# Lightpack5_6.net
KiCad netlist of a schematic drawn in EAGLE
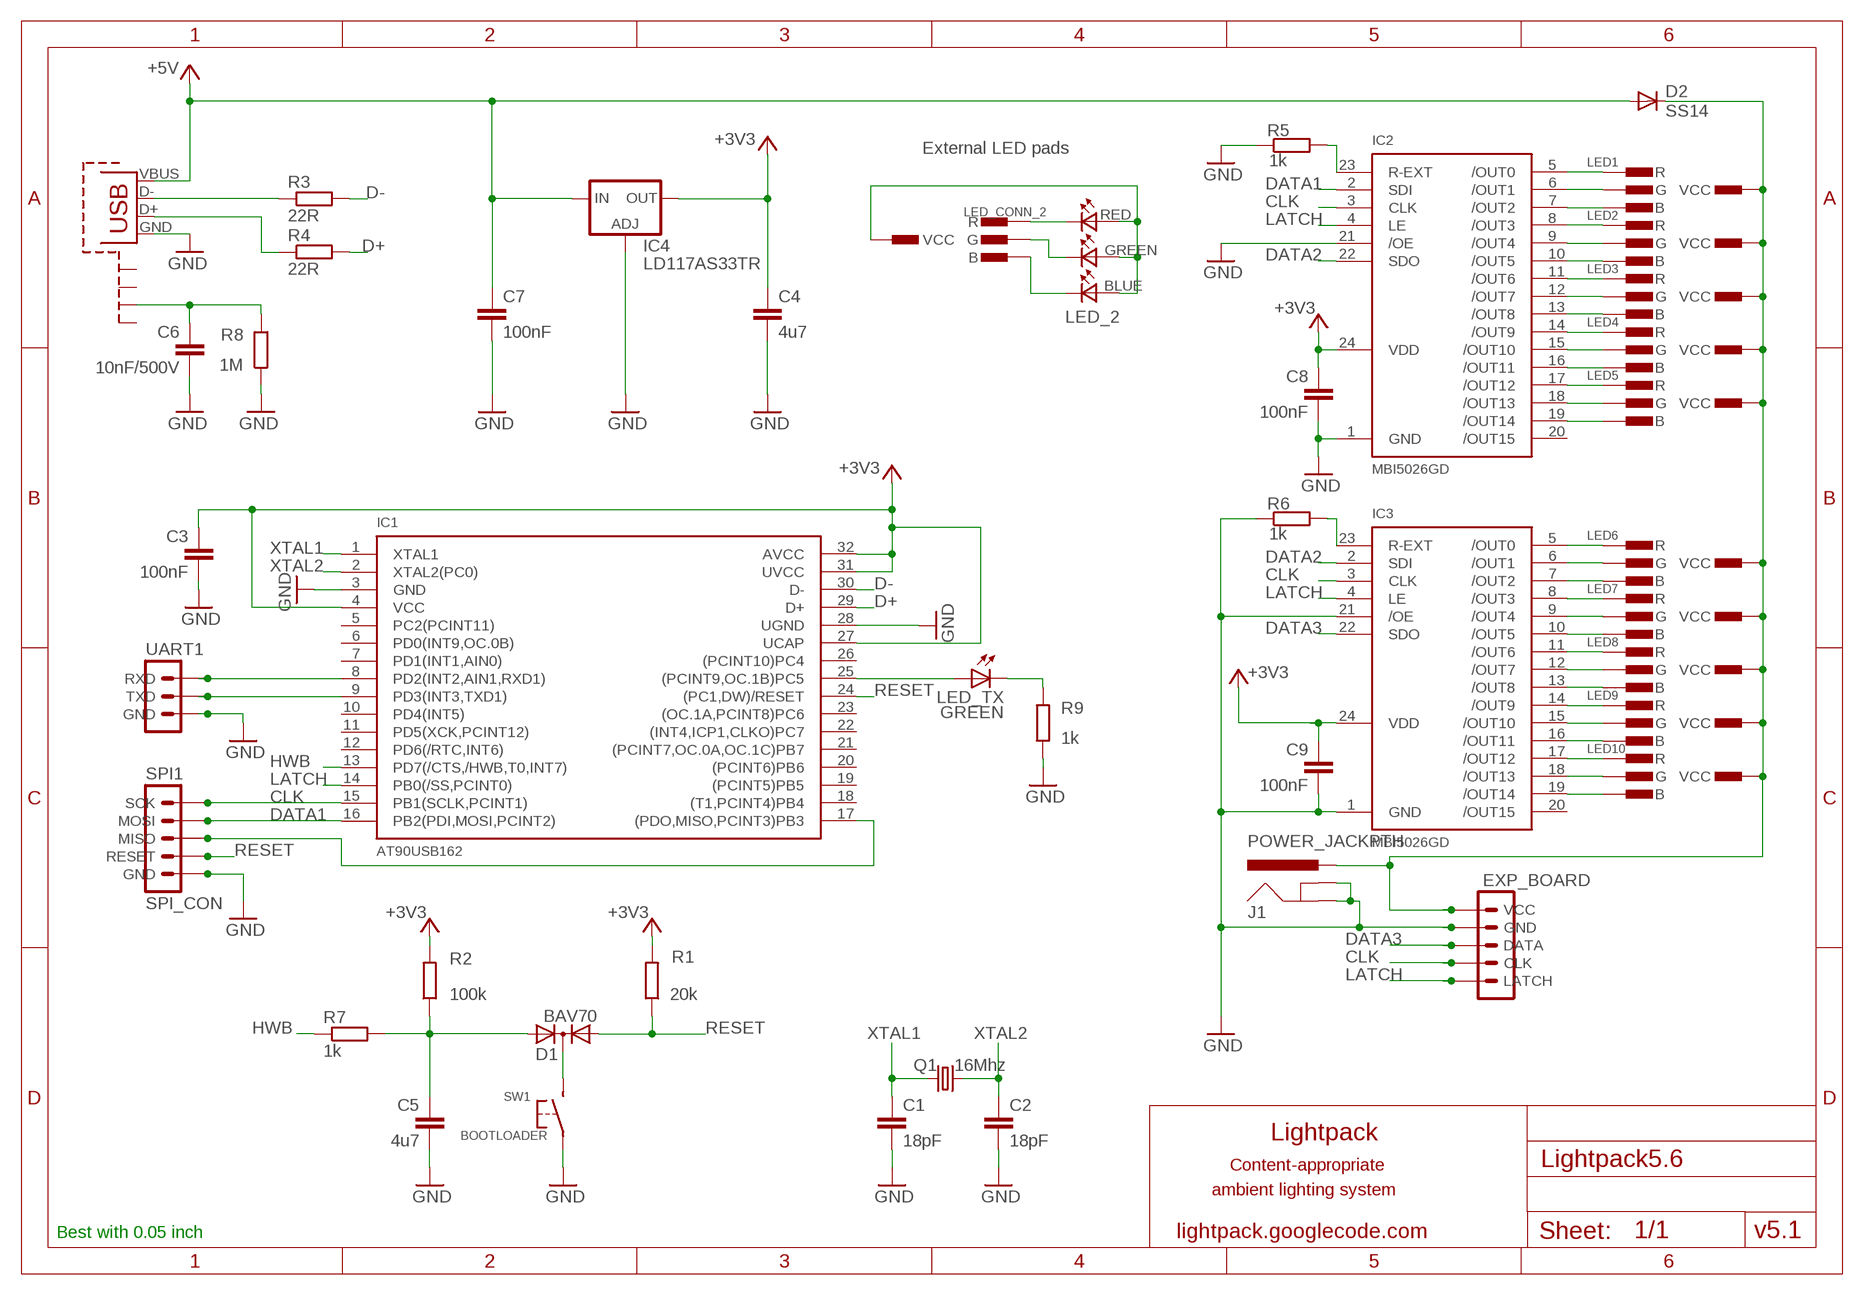
[diagram p0: schematic, sheet 1]

(export (version "E")
  (design (tool "Eeschema 10.0.6"))
  (components
    (comp (ref "C1")
      (value "18pF")
      (footprint "eagle-import:C1206")
      (libsource (lib "eagle-import") (part "C-EUC1206"))
    )
    (comp (ref "C2")
      (value "18pF")
      (footprint "eagle-import:C1206")
      (libsource (lib "eagle-import") (part "C-EUC1206"))
    )
    (comp (ref "C3")
      (value "100nF")
      (footprint "eagle-import:C1206")
      (libsource (lib "eagle-import") (part "C-EUC1206"))
    )
    (comp (ref "C4")
      (value "4u7")
      (footprint "eagle-import:C1206")
      (libsource (lib "eagle-import") (part "C-EUC1206"))
    )
    (comp (ref "C5")
      (value "4u7")
      (footprint "eagle-import:C1206")
      (libsource (lib "eagle-import") (part "C-EUC1206"))
    )
    (comp (ref "C6")
      (value "10nF/500V")
      (footprint "eagle-import:C1206")
      (libsource (lib "eagle-import") (part "C-EUC1206"))
    )
    (comp (ref "C7")
      (value "100nF")
      (footprint "eagle-import:C1206")
      (libsource (lib "eagle-import") (part "C-EUC1206"))
    )
    (comp (ref "C8")
      (value "100nF")
      (footprint "eagle-import:C1206")
      (libsource (lib "eagle-import") (part "C-EUC1206"))
    )
    (comp (ref "C9")
      (value "100nF")
      (footprint "eagle-import:C1206")
      (libsource (lib "eagle-import") (part "C-EUC1206"))
    )
    (comp (ref "D1")
      (value "BAV70")
      (footprint "eagle-import:SOT23")
      (libsource (lib "eagle-import") (part "DIODE-2AC|CASOT23"))
    )
    (comp (ref "D2")
      (value "SS14")
      (footprint "eagle-import:SMB")
      (libsource (lib "eagle-import") (part "DIODE-SMB"))
    )
    (comp (ref "EXP_BOARD")
      (value "MA05-1")
      (footprint "eagle-import:MA05-1")
      (libsource (lib "eagle-import") (part "MA05-1"))
    )
    (comp (ref "IC1")
      (value "AT90USB162")
      (footprint "eagle-import:TQFP32")
      (libsource (lib "eagle-import") (part "AT90USB162"))
    )
    (comp (ref "IC2")
      (value "MBI5026GD")
      (footprint "eagle-import:SOP24-300-1.27")
      (libsource (lib "eagle-import") (part "MBI5026GD"))
    )
    (comp (ref "IC3")
      (value "MBI5026GD")
      (footprint "eagle-import:SOP24-300-1.27")
      (libsource (lib "eagle-import") (part "MBI5026GD"))
    )
    (comp (ref "IC4")
      (value "LD117AS33TR")
      (footprint "eagle-import:SOT223")
      (libsource (lib "eagle-import") (part "LD117A?S33TR"))
    )
    (comp (ref "J1")
      (value "POWER_JACKPTH")
      (footprint "eagle-import:POWER_JACK_PTH")
      (libsource (lib "eagle-import") (part "POWER_JACKPTH"))
    )
    (comp (ref "LED1")
      (value "CON-RGB-LED")
      (footprint "eagle-import:CON-RGB-LED-TH")
      (libsource (lib "eagle-import") (part "CON-RGB-LED-TH"))
    )
    (comp (ref "LED2")
      (value "CON-RGB-LED")
      (footprint "eagle-import:CON-RGB-LED-TH")
      (libsource (lib "eagle-import") (part "CON-RGB-LED-TH"))
    )
    (comp (ref "LED3")
      (value "CON-RGB-LED")
      (footprint "eagle-import:CON-RGB-LED-TH")
      (libsource (lib "eagle-import") (part "CON-RGB-LED-TH"))
    )
    (comp (ref "LED4")
      (value "CON-RGB-LED")
      (footprint "eagle-import:CON-RGB-LED-TH")
      (libsource (lib "eagle-import") (part "CON-RGB-LED-TH"))
    )
    (comp (ref "LED5")
      (value "CON-RGB-LED")
      (footprint "eagle-import:CON-RGB-LED-TH")
      (libsource (lib "eagle-import") (part "CON-RGB-LED-TH"))
    )
    (comp (ref "LED6")
      (value "CON-RGB-LED")
      (footprint "eagle-import:CON-RGB-LED-TH")
      (libsource (lib "eagle-import") (part "CON-RGB-LED-TH"))
    )
    (comp (ref "LED7")
      (value "CON-RGB-LED")
      (footprint "eagle-import:CON-RGB-LED-TH")
      (libsource (lib "eagle-import") (part "CON-RGB-LED-TH"))
    )
    (comp (ref "LED8")
      (value "CON-RGB-LED")
      (footprint "eagle-import:CON-RGB-LED-TH")
      (libsource (lib "eagle-import") (part "CON-RGB-LED-TH"))
    )
    (comp (ref "LED9")
      (value "CON-RGB-LED")
      (footprint "eagle-import:CON-RGB-LED-TH")
      (libsource (lib "eagle-import") (part "CON-RGB-LED-TH"))
    )
    (comp (ref "LED10")
      (value "CON-RGB-LED")
      (footprint "eagle-import:CON-RGB-LED-TH")
      (libsource (lib "eagle-import") (part "CON-RGB-LED-TH"))
    )
    (comp (ref "LED_2")
      (value "TOPLED-3RF-W2SA50TS")
      (footprint "eagle-import:LP2C63-ST-RGB-SR0")
      (libsource (lib "eagle-import") (part "TOPLED-3RF-W2SA50TS"))
    )
    (comp (ref "LED_CONN_2")
      (value "CON-RGB-LED")
      (footprint "eagle-import:CON-RGB-LED-TH-EXT")
      (libsource (lib "eagle-import") (part "CON-RGB-LED-EXT"))
    )
    (comp (ref "LED_TX")
      (value "GREEN")
      (footprint "eagle-import:CHIPLED_0805")
      (libsource (lib "eagle-import") (part "LEDCHIPLED_0805"))
    )
    (comp (ref "Q1")
      (value "16Mhz")
      (footprint "eagle-import:HC49UP")
      (libsource (lib "eagle-import") (part "CRYSTALHC49UP"))
    )
    (comp (ref "R1")
      (value "20k")
      (footprint "eagle-import:R1206")
      (libsource (lib "eagle-import") (part "R-EU_R1206"))
    )
    (comp (ref "R2")
      (value "100k")
      (footprint "eagle-import:R1206")
      (libsource (lib "eagle-import") (part "R-EU_R1206_2"))
    )
    (comp (ref "R3")
      (value "22R")
      (footprint "eagle-import:R1206")
      (libsource (lib "eagle-import") (part "rcl_R-EU_R1206"))
    )
    (comp (ref "R4")
      (value "22R")
      (footprint "eagle-import:R1206")
      (libsource (lib "eagle-import") (part "rcl_R-EU_R1206"))
    )
    (comp (ref "R5")
      (value "1k")
      (footprint "eagle-import:R1206")
      (libsource (lib "eagle-import") (part "R-EU_R1206"))
    )
    (comp (ref "R6")
      (value "1k")
      (footprint "eagle-import:R1206")
      (libsource (lib "eagle-import") (part "R-EU_R1206"))
    )
    (comp (ref "R7")
      (value "1k")
      (footprint "eagle-import:R1206")
      (libsource (lib "eagle-import") (part "rcl_R-EU_R1206"))
    )
    (comp (ref "R8")
      (value "1M")
      (footprint "eagle-import:R1206")
      (libsource (lib "eagle-import") (part "rcl_R-EU_R1206"))
    )
    (comp (ref "R9")
      (value "1k")
      (footprint "eagle-import:R1206")
      (libsource (lib "eagle-import") (part "rcl_R-EU_R1206"))
    )
    (comp (ref "SPI1")
      (value "SPI_CON")
      (footprint "eagle-import:NXT_BRD")
      (libsource (lib "eagle-import") (part "SPI_CON"))
    )
    (comp (ref "SW1")
      (value "BOOTLOADER")
      (footprint "eagle-import:BUTTON-SMD")
      (libsource (lib "eagle-import") (part "BUTTON"))
    )
    (comp (ref "UART1")
      (value "UART3")
      (footprint "eagle-import:UART3")
      (libsource (lib "eagle-import") (part "UART3"))
    )
    (comp (ref "X1")
      (value "USB-MB-S")
      (footprint "eagle-import:USB-MB-S")
      (libsource (lib "eagle-import") (part "USB-MB-S"))
    )
  )
  (nets
    (net (code "1") (name "+3V3") (class "Default")
      (node (ref "C3") (pin "1") (pinfunction "1_1") (pintype "passive"))
      (node (ref "C4") (pin "1") (pinfunction "1_1") (pintype "passive"))
      (node (ref "C8") (pin "1") (pinfunction "1_1") (pintype "passive"))
      (node (ref "C9") (pin "1") (pinfunction "1_1") (pintype "passive"))
      (node (ref "IC1") (pin "27") (pinfunction "UCAP_27") (pintype "bidirectional"))
      (node (ref "IC1") (pin "31") (pinfunction "UVCC_31") (pintype "bidirectional"))
      (node (ref "IC1") (pin "32") (pinfunction "AVCC_32") (pintype "bidirectional"))
      (node (ref "IC1") (pin "4") (pinfunction "VCC_4") (pintype "bidirectional"))
      (node (ref "IC2") (pin "24") (pinfunction "VDD_24") (pintype "bidirectional"))
      (node (ref "IC3") (pin "24") (pinfunction "VDD_24") (pintype "bidirectional"))
      (node (ref "IC4") (pin "4") (pinfunction "OUT_4") (pintype "passive"))
      (node (ref "R1") (pin "2") (pinfunction "2_2") (pintype "passive"))
      (node (ref "R2") (pin "1") (pinfunction "2_1") (pintype "passive"))
    )
    (net (code "2") (name "+5V") (class "Default")
      (node (ref "C7") (pin "1") (pinfunction "1_1") (pintype "passive"))
      (node (ref "D2") (pin "A") (pinfunction "A_A") (pintype "passive"))
      (node (ref "IC4") (pin "3") (pinfunction "IN_3") (pintype "input"))
      (node (ref "X1") (pin "VBUS") (pinfunction "VBUS_VBUS") (pintype "bidirectional"))
    )
    (net (code "3") (name "/CLK") (class "Default")
      (node (ref "EXP_BOARD") (pin "2") (pinfunction "CLK_2") (pintype "passive"))
      (node (ref "IC1") (pin "15") (pinfunction "PB1(SCLK,PCINT1)_15") (pintype "bidirectional"))
      (node (ref "IC2") (pin "3") (pinfunction "CLK_3") (pintype "bidirectional"))
      (node (ref "IC3") (pin "3") (pinfunction "CLK_3") (pintype "bidirectional"))
      (node (ref "SPI1") (pin "2") (pinfunction "SCK_2") (pintype "passive"))
    )
    (net (code "4") (name "/D+") (class "Default")
      (node (ref "IC1") (pin "29") (pinfunction "D+_29") (pintype "bidirectional"))
      (node (ref "R4") (pin "2") (pinfunction "2_2") (pintype "passive"))
    )
    (net (code "5") (name "/D-") (class "Default")
      (node (ref "IC1") (pin "30") (pinfunction "D-_30") (pintype "bidirectional"))
      (node (ref "R3") (pin "2") (pinfunction "2_2") (pintype "passive"))
    )
    (net (code "6") (name "/DATA1") (class "Default")
      (node (ref "IC1") (pin "16") (pinfunction "PB2(PDI,MOSI,PCINT2)_16") (pintype "bidirectional"))
      (node (ref "IC2") (pin "2") (pinfunction "SDI_2") (pintype "bidirectional"))
      (node (ref "SPI1") (pin "3") (pinfunction "MOSI_3") (pintype "passive"))
    )
    (net (code "7") (name "/DATA2") (class "Default")
      (node (ref "IC2") (pin "22") (pinfunction "SDO_22") (pintype "bidirectional"))
      (node (ref "IC3") (pin "2") (pinfunction "SDI_2") (pintype "bidirectional"))
    )
    (net (code "8") (name "/DATA3") (class "Default")
      (node (ref "EXP_BOARD") (pin "3") (pinfunction "DATA_3") (pintype "passive"))
      (node (ref "IC3") (pin "22") (pinfunction "SDO_22") (pintype "bidirectional"))
    )
    (net (code "9") (name "/HWB") (class "Default")
      (node (ref "IC1") (pin "13") (pinfunction "PD7(/CTS,/HWB,T0,INT7)_13") (pintype "bidirectional"))
      (node (ref "R7") (pin "1") (pinfunction "1_1") (pintype "passive"))
    )
    (net (code "10") (name "/LATCH") (class "Default")
      (node (ref "EXP_BOARD") (pin "1") (pinfunction "LATCH_1") (pintype "passive"))
      (node (ref "IC1") (pin "14") (pinfunction "PB0(/SS,PCINT0)_14") (pintype "bidirectional"))
      (node (ref "IC2") (pin "4") (pinfunction "LE_4") (pintype "bidirectional"))
      (node (ref "IC3") (pin "4") (pinfunction "LE_4") (pintype "bidirectional"))
    )
    (net (code "11") (name "/RESET") (class "Default")
      (node (ref "D1") (pin "1") (pinfunction "A1_1") (pintype "passive"))
      (node (ref "IC1") (pin "24") (pinfunction "(PC1,DW)/RESET_24") (pintype "bidirectional"))
      (node (ref "R1") (pin "1") (pinfunction "1_1") (pintype "passive"))
      (node (ref "SPI1") (pin "5-R") (pinfunction "RESET_5-R") (pintype "passive"))
    )
    (net (code "12") (name "/XTAL1") (class "Default")
      (node (ref "C1") (pin "1") (pinfunction "1_1") (pintype "passive"))
      (node (ref "IC1") (pin "1") (pinfunction "XTAL1_1") (pintype "bidirectional"))
      (node (ref "Q1") (pin "1") (pinfunction "1_1") (pintype "passive"))
    )
    (net (code "13") (name "/XTAL2") (class "Default")
      (node (ref "C2") (pin "1") (pinfunction "1_1") (pintype "passive"))
      (node (ref "IC1") (pin "2") (pinfunction "XTAL2(PC0)_2") (pintype "bidirectional"))
      (node (ref "Q1") (pin "2") (pinfunction "2_2") (pintype "passive"))
    )
    (net (code "14") (name "GND") (class "Default")
      (node (ref "C1") (pin "2") (pinfunction "2_2") (pintype "passive"))
      (node (ref "C2") (pin "2") (pinfunction "2_2") (pintype "passive"))
      (node (ref "C3") (pin "2") (pinfunction "2_2") (pintype "passive"))
      (node (ref "C4") (pin "2") (pinfunction "2_2") (pintype "passive"))
      (node (ref "C5") (pin "2") (pinfunction "2_2") (pintype "passive"))
      (node (ref "C6") (pin "2") (pinfunction "2_2") (pintype "passive"))
      (node (ref "C7") (pin "2") (pinfunction "2_2") (pintype "passive"))
      (node (ref "C8") (pin "2") (pinfunction "2_2") (pintype "passive"))
      (node (ref "C9") (pin "2") (pinfunction "2_2") (pintype "passive"))
      (node (ref "EXP_BOARD") (pin "4") (pinfunction "GND_4") (pintype "passive"))
      (node (ref "IC1") (pin "28") (pinfunction "UGND_28") (pintype "bidirectional"))
      (node (ref "IC1") (pin "3") (pinfunction "GND_3") (pintype "bidirectional"))
      (node (ref "IC2") (pin "1") (pinfunction "GND_1") (pintype "bidirectional"))
      (node (ref "IC2") (pin "21") (pinfunction "/OE_21") (pintype "bidirectional"))
      (node (ref "IC3") (pin "1") (pinfunction "GND_1") (pintype "bidirectional"))
      (node (ref "IC3") (pin "21") (pinfunction "/OE_21") (pintype "bidirectional"))
      (node (ref "IC4") (pin "1") (pinfunction "ADJ_1") (pintype "input"))
      (node (ref "J1") (pin "GND") (pinfunction "GND_GND") (pintype "bidirectional"))
      (node (ref "J1") (pin "GNDBREAK") (pinfunction "GNDBREAK_GNDBREAK") (pintype "bidirectional"))
      (node (ref "R5") (pin "1") (pinfunction "1_1") (pintype "passive"))
      (node (ref "R6") (pin "1") (pinfunction "1_1") (pintype "passive"))
      (node (ref "R8") (pin "1") (pinfunction "1_1") (pintype "passive"))
      (node (ref "R9") (pin "1") (pinfunction "1_1") (pintype "passive"))
      (node (ref "SPI1") (pin "1-L") (pinfunction "GND_1-L") (pintype "passive"))
      (node (ref "SW1") (pin "1") (pinfunction "1_1") (pintype "passive"))
      (node (ref "UART1") (pin "1-L") (pinfunction "GND_1-L") (pintype "passive"))
      (node (ref "X1") (pin "GND") (pinfunction "GND_GND") (pintype "bidirectional"))
    )
    (net (code "15") (name "Net-(C6-Pad1)") (class "Default")
      (node (ref "C6") (pin "1") (pinfunction "1_1") (pintype "passive"))
      (node (ref "R8") (pin "2") (pinfunction "2_2") (pintype "passive"))
      (node (ref "X1") (pin "SHIELD3") (pinfunction "SHIELD3_SHIELD3") (pintype "bidirectional"))
    )
    (net (code "16") (name "Net-(D1-A2)") (class "Default")
      (node (ref "C5") (pin "1") (pinfunction "1_1") (pintype "passive"))
      (node (ref "D1") (pin "2") (pinfunction "A2_2") (pintype "passive"))
      (node (ref "R2") (pin "2") (pinfunction "1_2") (pintype "passive"))
      (node (ref "R7") (pin "2") (pinfunction "2_2") (pintype "passive"))
    )
    (net (code "17") (name "Net-(D1-C)") (class "Default")
      (node (ref "D1") (pin "3") (pinfunction "C_3") (pintype "passive"))
      (node (ref "SW1") (pin "2") (pinfunction "2_2") (pintype "passive"))
    )
    (net (code "18") (name "Net-(EXP_BOARD-VCC)") (class "Default")
      (node (ref "D2") (pin "C") (pinfunction "C_C") (pintype "passive"))
      (node (ref "EXP_BOARD") (pin "5") (pinfunction "VCC_5") (pintype "passive"))
      (node (ref "J1") (pin "PWR") (pinfunction "PWR_PWR") (pintype "bidirectional"))
      (node (ref "LED1") (pin "4.VCC") (pinfunction "VCC_4.VCC") (pintype "bidirectional"))
      (node (ref "LED10") (pin "4.VCC") (pinfunction "VCC_4.VCC") (pintype "bidirectional"))
      (node (ref "LED2") (pin "4.VCC") (pinfunction "VCC_4.VCC") (pintype "bidirectional"))
      (node (ref "LED3") (pin "4.VCC") (pinfunction "VCC_4.VCC") (pintype "bidirectional"))
      (node (ref "LED4") (pin "4.VCC") (pinfunction "VCC_4.VCC") (pintype "bidirectional"))
      (node (ref "LED5") (pin "4.VCC") (pinfunction "VCC_4.VCC") (pintype "bidirectional"))
      (node (ref "LED6") (pin "4.VCC") (pinfunction "VCC_4.VCC") (pintype "bidirectional"))
      (node (ref "LED7") (pin "4.VCC") (pinfunction "VCC_4.VCC") (pintype "bidirectional"))
      (node (ref "LED8") (pin "4.VCC") (pinfunction "VCC_4.VCC") (pintype "bidirectional"))
      (node (ref "LED9") (pin "4.VCC") (pinfunction "VCC_4.VCC") (pintype "bidirectional"))
    )
    (net (code "19") (name "Net-(IC1-(PCINT9,OC.1B)PC5)") (class "Default")
      (node (ref "IC1") (pin "25") (pinfunction "(PCINT9,OC.1B)PC5_25") (pintype "bidirectional"))
      (node (ref "LED_TX") (pin "A") (pinfunction "A_A") (pintype "passive"))
    )
    (net (code "20") (name "Net-(IC1-(PDO,MISO,PCINT3)PB3)") (class "Default")
      (node (ref "IC1") (pin "17") (pinfunction "(PDO,MISO,PCINT3)PB3_17") (pintype "bidirectional"))
      (node (ref "SPI1") (pin "4") (pinfunction "MISO_4") (pintype "passive"))
    )
    (net (code "21") (name "Net-(IC1-PD2(INT2,AIN1,RXD1))") (class "Default")
      (node (ref "IC1") (pin "8") (pinfunction "PD2(INT2,AIN1,RXD1)_8") (pintype "bidirectional"))
      (node (ref "UART1") (pin "2") (pinfunction "RXD_2") (pintype "passive"))
    )
    (net (code "22") (name "Net-(IC1-PD3(INT3,TXD1))") (class "Default")
      (node (ref "IC1") (pin "9") (pinfunction "PD3(INT3,TXD1)_9") (pintype "bidirectional"))
      (node (ref "UART1") (pin "3-R") (pinfunction "TXD_3-R") (pintype "passive"))
    )
    (net (code "23") (name "Net-(IC2-R-EXT)") (class "Default")
      (node (ref "IC2") (pin "23") (pinfunction "R-EXT_23") (pintype "bidirectional"))
      (node (ref "R5") (pin "2") (pinfunction "2_2") (pintype "passive"))
    )
    (net (code "24") (name "Net-(IC2-{slash}OUT0)") (class "Default")
      (node (ref "IC2") (pin "5") (pinfunction "/OUT0_5") (pintype "bidirectional"))
      (node (ref "LED1") (pin "3.R") (pinfunction "R_3.R") (pintype "bidirectional"))
    )
    (net (code "25") (name "Net-(IC2-{slash}OUT1)") (class "Default")
      (node (ref "IC2") (pin "6") (pinfunction "/OUT1_6") (pintype "bidirectional"))
      (node (ref "LED1") (pin "2.G") (pinfunction "G_2.G") (pintype "bidirectional"))
    )
    (net (code "26") (name "Net-(IC2-{slash}OUT2)") (class "Default")
      (node (ref "IC2") (pin "7") (pinfunction "/OUT2_7") (pintype "bidirectional"))
      (node (ref "LED1") (pin "1.B") (pinfunction "B_1.B") (pintype "bidirectional"))
    )
    (net (code "27") (name "Net-(IC2-{slash}OUT3)") (class "Default")
      (node (ref "IC2") (pin "8") (pinfunction "/OUT3_8") (pintype "bidirectional"))
      (node (ref "LED2") (pin "3.R") (pinfunction "R_3.R") (pintype "bidirectional"))
    )
    (net (code "28") (name "Net-(IC2-{slash}OUT4)") (class "Default")
      (node (ref "IC2") (pin "9") (pinfunction "/OUT4_9") (pintype "bidirectional"))
      (node (ref "LED2") (pin "2.G") (pinfunction "G_2.G") (pintype "bidirectional"))
    )
    (net (code "29") (name "Net-(IC2-{slash}OUT5)") (class "Default")
      (node (ref "IC2") (pin "10") (pinfunction "/OUT5_10") (pintype "bidirectional"))
      (node (ref "LED2") (pin "1.B") (pinfunction "B_1.B") (pintype "bidirectional"))
    )
    (net (code "30") (name "Net-(IC2-{slash}OUT6)") (class "Default")
      (node (ref "IC2") (pin "11") (pinfunction "/OUT6_11") (pintype "bidirectional"))
      (node (ref "LED3") (pin "3.R") (pinfunction "R_3.R") (pintype "bidirectional"))
    )
    (net (code "31") (name "Net-(IC2-{slash}OUT7)") (class "Default")
      (node (ref "IC2") (pin "12") (pinfunction "/OUT7_12") (pintype "bidirectional"))
      (node (ref "LED3") (pin "2.G") (pinfunction "G_2.G") (pintype "bidirectional"))
    )
    (net (code "32") (name "Net-(IC2-{slash}OUT8)") (class "Default")
      (node (ref "IC2") (pin "13") (pinfunction "/OUT8_13") (pintype "bidirectional"))
      (node (ref "LED3") (pin "1.B") (pinfunction "B_1.B") (pintype "bidirectional"))
    )
    (net (code "33") (name "Net-(IC2-{slash}OUT9)") (class "Default")
      (node (ref "IC2") (pin "14") (pinfunction "/OUT9_14") (pintype "bidirectional"))
      (node (ref "LED4") (pin "3.R") (pinfunction "R_3.R") (pintype "bidirectional"))
    )
    (net (code "34") (name "Net-(IC2-{slash}OUT10)") (class "Default")
      (node (ref "IC2") (pin "15") (pinfunction "/OUT10_15") (pintype "bidirectional"))
      (node (ref "LED4") (pin "2.G") (pinfunction "G_2.G") (pintype "bidirectional"))
    )
    (net (code "35") (name "Net-(IC2-{slash}OUT11)") (class "Default")
      (node (ref "IC2") (pin "16") (pinfunction "/OUT11_16") (pintype "bidirectional"))
      (node (ref "LED4") (pin "1.B") (pinfunction "B_1.B") (pintype "bidirectional"))
    )
    (net (code "36") (name "Net-(IC2-{slash}OUT12)") (class "Default")
      (node (ref "IC2") (pin "17") (pinfunction "/OUT12_17") (pintype "bidirectional"))
      (node (ref "LED5") (pin "3.R") (pinfunction "R_3.R") (pintype "bidirectional"))
    )
    (net (code "37") (name "Net-(IC2-{slash}OUT13)") (class "Default")
      (node (ref "IC2") (pin "18") (pinfunction "/OUT13_18") (pintype "bidirectional"))
      (node (ref "LED5") (pin "2.G") (pinfunction "G_2.G") (pintype "bidirectional"))
    )
    (net (code "38") (name "Net-(IC2-{slash}OUT14)") (class "Default")
      (node (ref "IC2") (pin "19") (pinfunction "/OUT14_19") (pintype "bidirectional"))
      (node (ref "LED5") (pin "1.B") (pinfunction "B_1.B") (pintype "bidirectional"))
    )
    (net (code "39") (name "Net-(IC3-R-EXT)") (class "Default")
      (node (ref "IC3") (pin "23") (pinfunction "R-EXT_23") (pintype "bidirectional"))
      (node (ref "R6") (pin "2") (pinfunction "2_2") (pintype "passive"))
    )
    (net (code "40") (name "Net-(IC3-{slash}OUT0)") (class "Default")
      (node (ref "IC3") (pin "5") (pinfunction "/OUT0_5") (pintype "bidirectional"))
      (node (ref "LED6") (pin "3.R") (pinfunction "R_3.R") (pintype "bidirectional"))
    )
    (net (code "41") (name "Net-(IC3-{slash}OUT1)") (class "Default")
      (node (ref "IC3") (pin "6") (pinfunction "/OUT1_6") (pintype "bidirectional"))
      (node (ref "LED6") (pin "2.G") (pinfunction "G_2.G") (pintype "bidirectional"))
    )
    (net (code "42") (name "Net-(IC3-{slash}OUT2)") (class "Default")
      (node (ref "IC3") (pin "7") (pinfunction "/OUT2_7") (pintype "bidirectional"))
      (node (ref "LED6") (pin "1.B") (pinfunction "B_1.B") (pintype "bidirectional"))
    )
    (net (code "43") (name "Net-(IC3-{slash}OUT3)") (class "Default")
      (node (ref "IC3") (pin "8") (pinfunction "/OUT3_8") (pintype "bidirectional"))
      (node (ref "LED7") (pin "3.R") (pinfunction "R_3.R") (pintype "bidirectional"))
    )
    (net (code "44") (name "Net-(IC3-{slash}OUT4)") (class "Default")
      (node (ref "IC3") (pin "9") (pinfunction "/OUT4_9") (pintype "bidirectional"))
      (node (ref "LED7") (pin "2.G") (pinfunction "G_2.G") (pintype "bidirectional"))
    )
    (net (code "45") (name "Net-(IC3-{slash}OUT5)") (class "Default")
      (node (ref "IC3") (pin "10") (pinfunction "/OUT5_10") (pintype "bidirectional"))
      (node (ref "LED7") (pin "1.B") (pinfunction "B_1.B") (pintype "bidirectional"))
    )
    (net (code "46") (name "Net-(IC3-{slash}OUT6)") (class "Default")
      (node (ref "IC3") (pin "11") (pinfunction "/OUT6_11") (pintype "bidirectional"))
      (node (ref "LED8") (pin "3.R") (pinfunction "R_3.R") (pintype "bidirectional"))
    )
    (net (code "47") (name "Net-(IC3-{slash}OUT7)") (class "Default")
      (node (ref "IC3") (pin "12") (pinfunction "/OUT7_12") (pintype "bidirectional"))
      (node (ref "LED8") (pin "2.G") (pinfunction "G_2.G") (pintype "bidirectional"))
    )
    (net (code "48") (name "Net-(IC3-{slash}OUT8)") (class "Default")
      (node (ref "IC3") (pin "13") (pinfunction "/OUT8_13") (pintype "bidirectional"))
      (node (ref "LED8") (pin "1.B") (pinfunction "B_1.B") (pintype "bidirectional"))
    )
    (net (code "49") (name "Net-(IC3-{slash}OUT9)") (class "Default")
      (node (ref "IC3") (pin "14") (pinfunction "/OUT9_14") (pintype "bidirectional"))
      (node (ref "LED9") (pin "3.R") (pinfunction "R_3.R") (pintype "bidirectional"))
    )
    (net (code "50") (name "Net-(IC3-{slash}OUT10)") (class "Default")
      (node (ref "IC3") (pin "15") (pinfunction "/OUT10_15") (pintype "bidirectional"))
      (node (ref "LED9") (pin "2.G") (pinfunction "G_2.G") (pintype "bidirectional"))
    )
    (net (code "51") (name "Net-(IC3-{slash}OUT11)") (class "Default")
      (node (ref "IC3") (pin "16") (pinfunction "/OUT11_16") (pintype "bidirectional"))
      (node (ref "LED9") (pin "1.B") (pinfunction "B_1.B") (pintype "bidirectional"))
    )
    (net (code "52") (name "Net-(IC3-{slash}OUT12)") (class "Default")
      (node (ref "IC3") (pin "17") (pinfunction "/OUT12_17") (pintype "bidirectional"))
      (node (ref "LED10") (pin "3.R") (pinfunction "R_3.R") (pintype "bidirectional"))
    )
    (net (code "53") (name "Net-(IC3-{slash}OUT13)") (class "Default")
      (node (ref "IC3") (pin "18") (pinfunction "/OUT13_18") (pintype "bidirectional"))
      (node (ref "LED10") (pin "2.G") (pinfunction "G_2.G") (pintype "bidirectional"))
    )
    (net (code "54") (name "Net-(IC3-{slash}OUT14)") (class "Default")
      (node (ref "IC3") (pin "19") (pinfunction "/OUT14_19") (pintype "bidirectional"))
      (node (ref "LED10") (pin "1.B") (pinfunction "B_1.B") (pintype "bidirectional"))
    )
    (net (code "55") (name "Net-(LED_CONN_2-B)") (class "Default")
      (node (ref "LED_2") (pin "CBLUE") (pinfunction "CBLUE_CBLUE") (pintype "passive"))
      (node (ref "LED_CONN_2") (pin "1.B") (pinfunction "B_1.B") (pintype "bidirectional"))
    )
    (net (code "56") (name "Net-(LED_CONN_2-G)") (class "Default")
      (node (ref "LED_2") (pin "CGREEN") (pinfunction "CGREEN_CGREEN") (pintype "passive"))
      (node (ref "LED_CONN_2") (pin "2.G") (pinfunction "G_2.G") (pintype "bidirectional"))
    )
    (net (code "57") (name "Net-(LED_CONN_2-R)") (class "Default")
      (node (ref "LED_2") (pin "CRED") (pinfunction "CRED_CRED") (pintype "passive"))
      (node (ref "LED_CONN_2") (pin "3.R") (pinfunction "R_3.R") (pintype "bidirectional"))
    )
    (net (code "58") (name "Net-(LED_CONN_2-VCC)") (class "Default")
      (node (ref "LED_2") (pin "BLUE") (pinfunction "BLUE_BLUE") (pintype "passive"))
      (node (ref "LED_2") (pin "GREEN") (pinfunction "GREEN_GREEN") (pintype "passive"))
      (node (ref "LED_2") (pin "RED") (pinfunction "RED_RED") (pintype "passive"))
      (node (ref "LED_CONN_2") (pin "4.VCC") (pinfunction "VCC_4.VCC") (pintype "bidirectional"))
    )
    (net (code "59") (name "Net-(LED_TX-PadC)") (class "Default")
      (node (ref "LED_TX") (pin "C") (pinfunction "C_C") (pintype "passive"))
      (node (ref "R9") (pin "2") (pinfunction "2_2") (pintype "passive"))
    )
    (net (code "60") (name "Net-(R3-Pad1)") (class "Default")
      (node (ref "R3") (pin "1") (pinfunction "1_1") (pintype "passive"))
      (node (ref "X1") (pin "D-") (pinfunction "D-_D-") (pintype "bidirectional"))
    )
    (net (code "61") (name "Net-(R4-Pad1)") (class "Default")
      (node (ref "R4") (pin "1") (pinfunction "1_1") (pintype "passive"))
      (node (ref "X1") (pin "D+") (pinfunction "D+_D+") (pintype "bidirectional"))
    )
    (net (code "62") (name "unconnected-(IC1-(INT4,ICP1,CLKO)PC7-Pad22)") (class "Default")
      (node (ref "IC1") (pin "22") (pinfunction "(INT4,ICP1,CLKO)PC7_22") (pintype "bidirectional"))
    )
    (net (code "63") (name "unconnected-(IC1-(OC.1A,PCINT8)PC6-Pad23)") (class "Default")
      (node (ref "IC1") (pin "23") (pinfunction "(OC.1A,PCINT8)PC6_23") (pintype "bidirectional"))
    )
    (net (code "64") (name "unconnected-(IC1-(PCINT5)PB5-Pad19)") (class "Default")
      (node (ref "IC1") (pin "19") (pinfunction "(PCINT5)PB5_19") (pintype "bidirectional"))
    )
    (net (code "65") (name "unconnected-(IC1-(PCINT6)PB6-Pad20)") (class "Default")
      (node (ref "IC1") (pin "20") (pinfunction "(PCINT6)PB6_20") (pintype "bidirectional"))
    )
    (net (code "66") (name "unconnected-(IC1-(PCINT7,OC.0A,OC.1C)PB7-Pad21)") (class "Default")
      (node (ref "IC1") (pin "21") (pinfunction "(PCINT7,OC.0A,OC.1C)PB7_21") (pintype "bidirectional"))
    )
    (net (code "67") (name "unconnected-(IC1-(PCINT10)PC4-Pad26)") (class "Default")
      (node (ref "IC1") (pin "26") (pinfunction "(PCINT10)PC4_26") (pintype "bidirectional"))
    )
    (net (code "68") (name "unconnected-(IC1-(T1,PCINT4)PB4-Pad18)") (class "Default")
      (node (ref "IC1") (pin "18") (pinfunction "(T1,PCINT4)PB4_18") (pintype "bidirectional"))
    )
    (net (code "69") (name "unconnected-(IC1-PC2(PCINT11)-Pad5)") (class "Default")
      (node (ref "IC1") (pin "5") (pinfunction "PC2(PCINT11)_5") (pintype "bidirectional"))
    )
    (net (code "70") (name "unconnected-(IC1-PD0(INT9,OC.0B)-Pad6)") (class "Default")
      (node (ref "IC1") (pin "6") (pinfunction "PD0(INT9,OC.0B)_6") (pintype "bidirectional"))
    )
    (net (code "71") (name "unconnected-(IC1-PD1(INT1,AIN0)-Pad7)") (class "Default")
      (node (ref "IC1") (pin "7") (pinfunction "PD1(INT1,AIN0)_7") (pintype "bidirectional"))
    )
    (net (code "72") (name "unconnected-(IC1-PD4(INT5)-Pad10)") (class "Default")
      (node (ref "IC1") (pin "10") (pinfunction "PD4(INT5)_10") (pintype "bidirectional"))
    )
    (net (code "73") (name "unconnected-(IC1-PD5(XCK,PCINT12)-Pad11)") (class "Default")
      (node (ref "IC1") (pin "11") (pinfunction "PD5(XCK,PCINT12)_11") (pintype "bidirectional"))
    )
    (net (code "74") (name "unconnected-(IC1-PD6({slash}RTC,INT6)-Pad12)") (class "Default")
      (node (ref "IC1") (pin "12") (pinfunction "PD6(/RTC,INT6)_12") (pintype "bidirectional"))
    )
    (net (code "75") (name "unconnected-(IC2-{slash}OUT15-Pad20)") (class "Default")
      (node (ref "IC2") (pin "20") (pinfunction "/OUT15_20") (pintype "bidirectional"))
    )
    (net (code "76") (name "unconnected-(IC3-{slash}OUT15-Pad20)") (class "Default")
      (node (ref "IC3") (pin "20") (pinfunction "/OUT15_20") (pintype "bidirectional"))
    )
    (net (code "77") (name "unconnected-(X1-PadSHIELD1)") (class "Default")
      (node (ref "X1") (pin "SHIELD1") (pinfunction "SHIELD1_SHIELD1") (pintype "bidirectional"))
    )
    (net (code "78") (name "unconnected-(X1-PadSHIELD2)") (class "Default")
      (node (ref "X1") (pin "SHIELD2") (pinfunction "SHIELD2_SHIELD2") (pintype "bidirectional"))
    )
    (net (code "79") (name "unconnected-(X1-PadSHIELD4)") (class "Default")
      (node (ref "X1") (pin "SHIELD4") (pinfunction "SHIELD4_SHIELD4") (pintype "bidirectional"))
    )
  )
)
